# Voicecard-Template.net
KiCad netlist of a schematic drawn in EAGLE
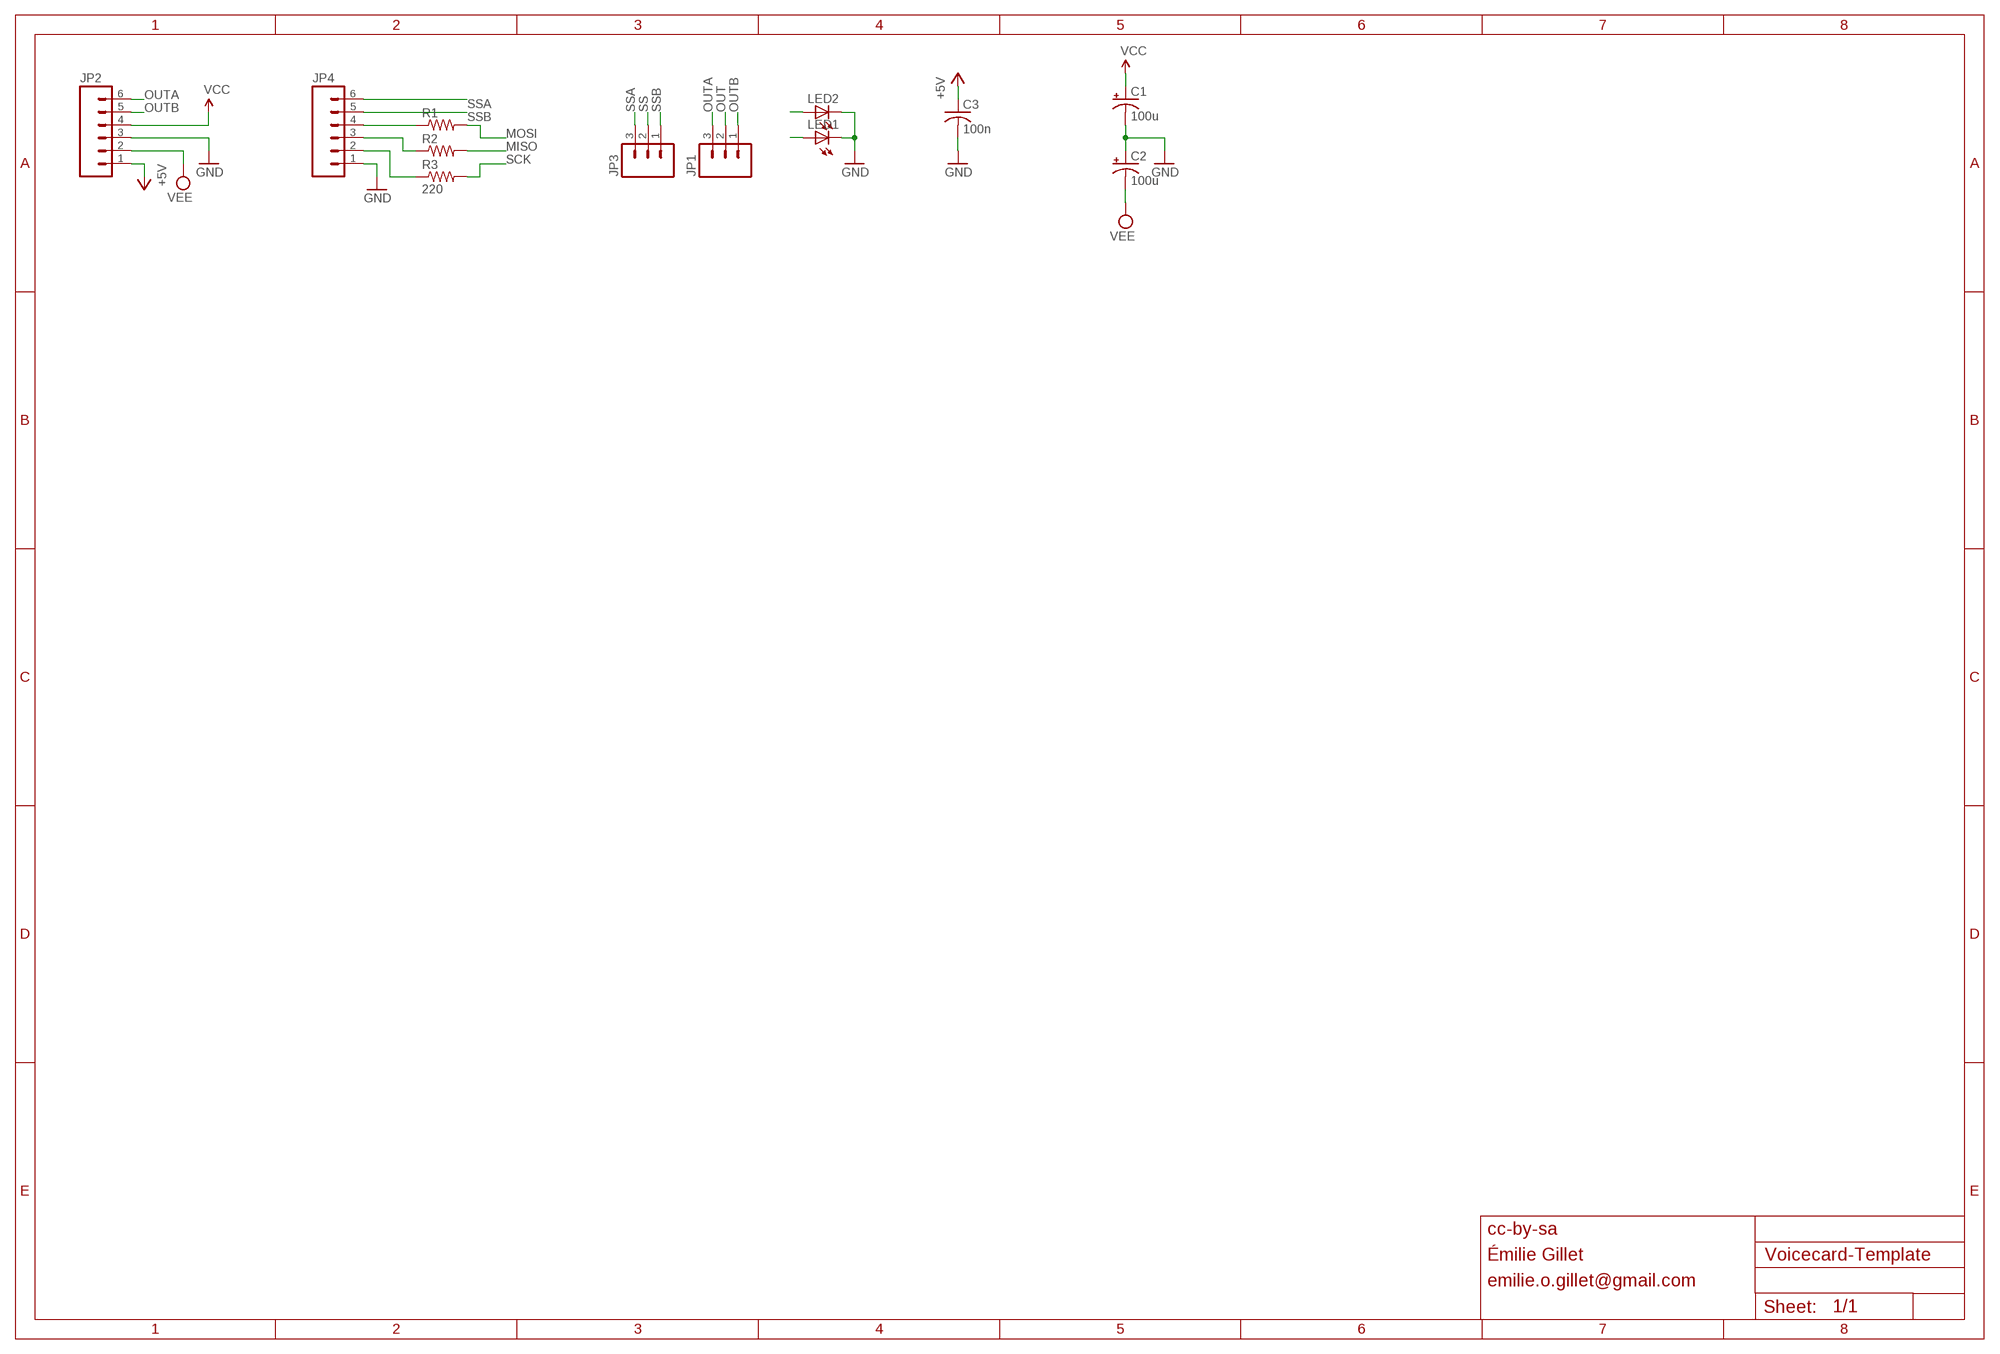
[diagram p0: schematic, sheet 1]

(export (version "E")
  (design (tool "Eeschema 10.0.6"))
  (components
    (comp (ref "C1")
      (value "100u")
      (footprint "eagle-import:E2,5-6")
      (libsource (lib "eagle-import") (part "CPOL-USE2.5-6"))
    )
    (comp (ref "C2")
      (value "100u")
      (footprint "eagle-import:E2,5-6")
      (libsource (lib "eagle-import") (part "CPOL-USE2.5-6"))
    )
    (comp (ref "C3")
      (value "100n")
      (footprint "eagle-import:C025-025X050")
      (libsource (lib "eagle-import") (part "C-US025-025X050"))
    )
    (comp (ref "JP1")
      (value "M03PTH")
      (footprint "eagle-import:1X03")
      (libsource (lib "eagle-import") (part "M03PTH"))
    )
    (comp (ref "JP2")
      (value "M06SIP")
      (footprint "eagle-import:1X06")
      (libsource (lib "eagle-import") (part "M06SIP"))
    )
    (comp (ref "JP3")
      (value "M03PTH")
      (footprint "eagle-import:1X03")
      (libsource (lib "eagle-import") (part "M03PTH"))
    )
    (comp (ref "JP4")
      (value "M06SIP")
      (footprint "eagle-import:1X06")
      (libsource (lib "eagle-import") (part "M06SIP"))
    )
    (comp (ref "LED1")
      (value "LED3MM")
      (footprint "eagle-import:LED3MM")
      (libsource (lib "eagle-import") (part "LED3MM"))
    )
    (comp (ref "LED2")
      (value "LED3MM")
      (footprint "eagle-import:LED3MM")
      (libsource (lib "eagle-import") (part "LED3MM"))
    )
    (comp (ref "R1")
      (value "220")
      (footprint "eagle-import:0204_7")
      (libsource (lib "eagle-import") (part "R-US_0204/7"))
    )
    (comp (ref "R2")
      (value "220")
      (footprint "eagle-import:0204_7")
      (libsource (lib "eagle-import") (part "R-US_0204/7"))
    )
    (comp (ref "R3")
      (value "220")
      (footprint "eagle-import:0204_7")
      (libsource (lib "eagle-import") (part "R-US_0204/7"))
    )
  )
  (nets
    (net (code "1") (name "+5V") (class "Default")
      (node (ref "C3") (pin "1") (pinfunction "1_1") (pintype "passive"))
      (node (ref "JP2") (pin "1") (pinfunction "1_1") (pintype "passive"))
    )
    (net (code "2") (name "/MISO") (class "Default")
      (node (ref "R2") (pin "2") (pinfunction "2_2") (pintype "passive"))
    )
    (net (code "3") (name "/MOSI") (class "Default")
      (node (ref "R1") (pin "2") (pinfunction "2_2") (pintype "passive"))
    )
    (net (code "4") (name "/OUT") (class "Default")
      (node (ref "JP1") (pin "2") (pinfunction "2_2") (pintype "passive"))
    )
    (net (code "5") (name "/OUTA") (class "Default")
      (node (ref "JP1") (pin "3") (pinfunction "3_3") (pintype "passive"))
      (node (ref "JP2") (pin "6") (pinfunction "6_6") (pintype "passive"))
    )
    (net (code "6") (name "/OUTB") (class "Default")
      (node (ref "JP1") (pin "1") (pinfunction "1_1") (pintype "passive"))
      (node (ref "JP2") (pin "5") (pinfunction "5_5") (pintype "passive"))
    )
    (net (code "7") (name "/SCK") (class "Default")
      (node (ref "R3") (pin "2") (pinfunction "2_2") (pintype "passive"))
    )
    (net (code "8") (name "/SS") (class "Default")
      (node (ref "JP3") (pin "2") (pinfunction "2_2") (pintype "passive"))
    )
    (net (code "9") (name "/SSA") (class "Default")
      (node (ref "JP3") (pin "3") (pinfunction "3_3") (pintype "passive"))
      (node (ref "JP4") (pin "6") (pinfunction "6_6") (pintype "passive"))
    )
    (net (code "10") (name "/SSB") (class "Default")
      (node (ref "JP3") (pin "1") (pinfunction "1_1") (pintype "passive"))
      (node (ref "JP4") (pin "5") (pinfunction "5_5") (pintype "passive"))
    )
    (net (code "11") (name "GND") (class "Default")
      (node (ref "C1") (pin "-") (pinfunction "-_-") (pintype "passive"))
      (node (ref "C2") (pin "+") (pinfunction "+_+") (pintype "passive"))
      (node (ref "C3") (pin "2") (pinfunction "2_2") (pintype "passive"))
      (node (ref "JP2") (pin "3") (pinfunction "3_3") (pintype "passive"))
      (node (ref "JP4") (pin "1") (pinfunction "1_1") (pintype "passive"))
      (node (ref "LED1") (pin "K") (pinfunction "C_K") (pintype "passive"))
      (node (ref "LED2") (pin "K") (pinfunction "C_K") (pintype "passive"))
    )
    (net (code "12") (name "Net-(JP4-Pad2)") (class "Default")
      (node (ref "JP4") (pin "2") (pinfunction "2_2") (pintype "passive"))
      (node (ref "R3") (pin "1") (pinfunction "1_1") (pintype "passive"))
    )
    (net (code "13") (name "Net-(JP4-Pad3)") (class "Default")
      (node (ref "JP4") (pin "3") (pinfunction "3_3") (pintype "passive"))
      (node (ref "R2") (pin "1") (pinfunction "1_1") (pintype "passive"))
    )
    (net (code "14") (name "Net-(JP4-Pad4)") (class "Default")
      (node (ref "JP4") (pin "4") (pinfunction "4_4") (pintype "passive"))
      (node (ref "R1") (pin "1") (pinfunction "1_1") (pintype "passive"))
    )
    (net (code "15") (name "VCC") (class "Default")
      (node (ref "C1") (pin "+") (pinfunction "+_+") (pintype "passive"))
      (node (ref "JP2") (pin "4") (pinfunction "4_4") (pintype "passive"))
    )
    (net (code "16") (name "VEE") (class "Default")
      (node (ref "C2") (pin "-") (pinfunction "-_-") (pintype "passive"))
      (node (ref "JP2") (pin "2") (pinfunction "2_2") (pintype "passive"))
    )
    (net (code "17") (name "unconnected-(LED1-PadA)") (class "Default")
      (node (ref "LED1") (pin "A") (pinfunction "A_A") (pintype "passive"))
    )
    (net (code "18") (name "unconnected-(LED2-PadA)") (class "Default")
      (node (ref "LED2") (pin "A") (pinfunction "A_A") (pintype "passive"))
    )
  )
)
